# SB.net
KiCad netlist of a schematic drawn in EAGLE
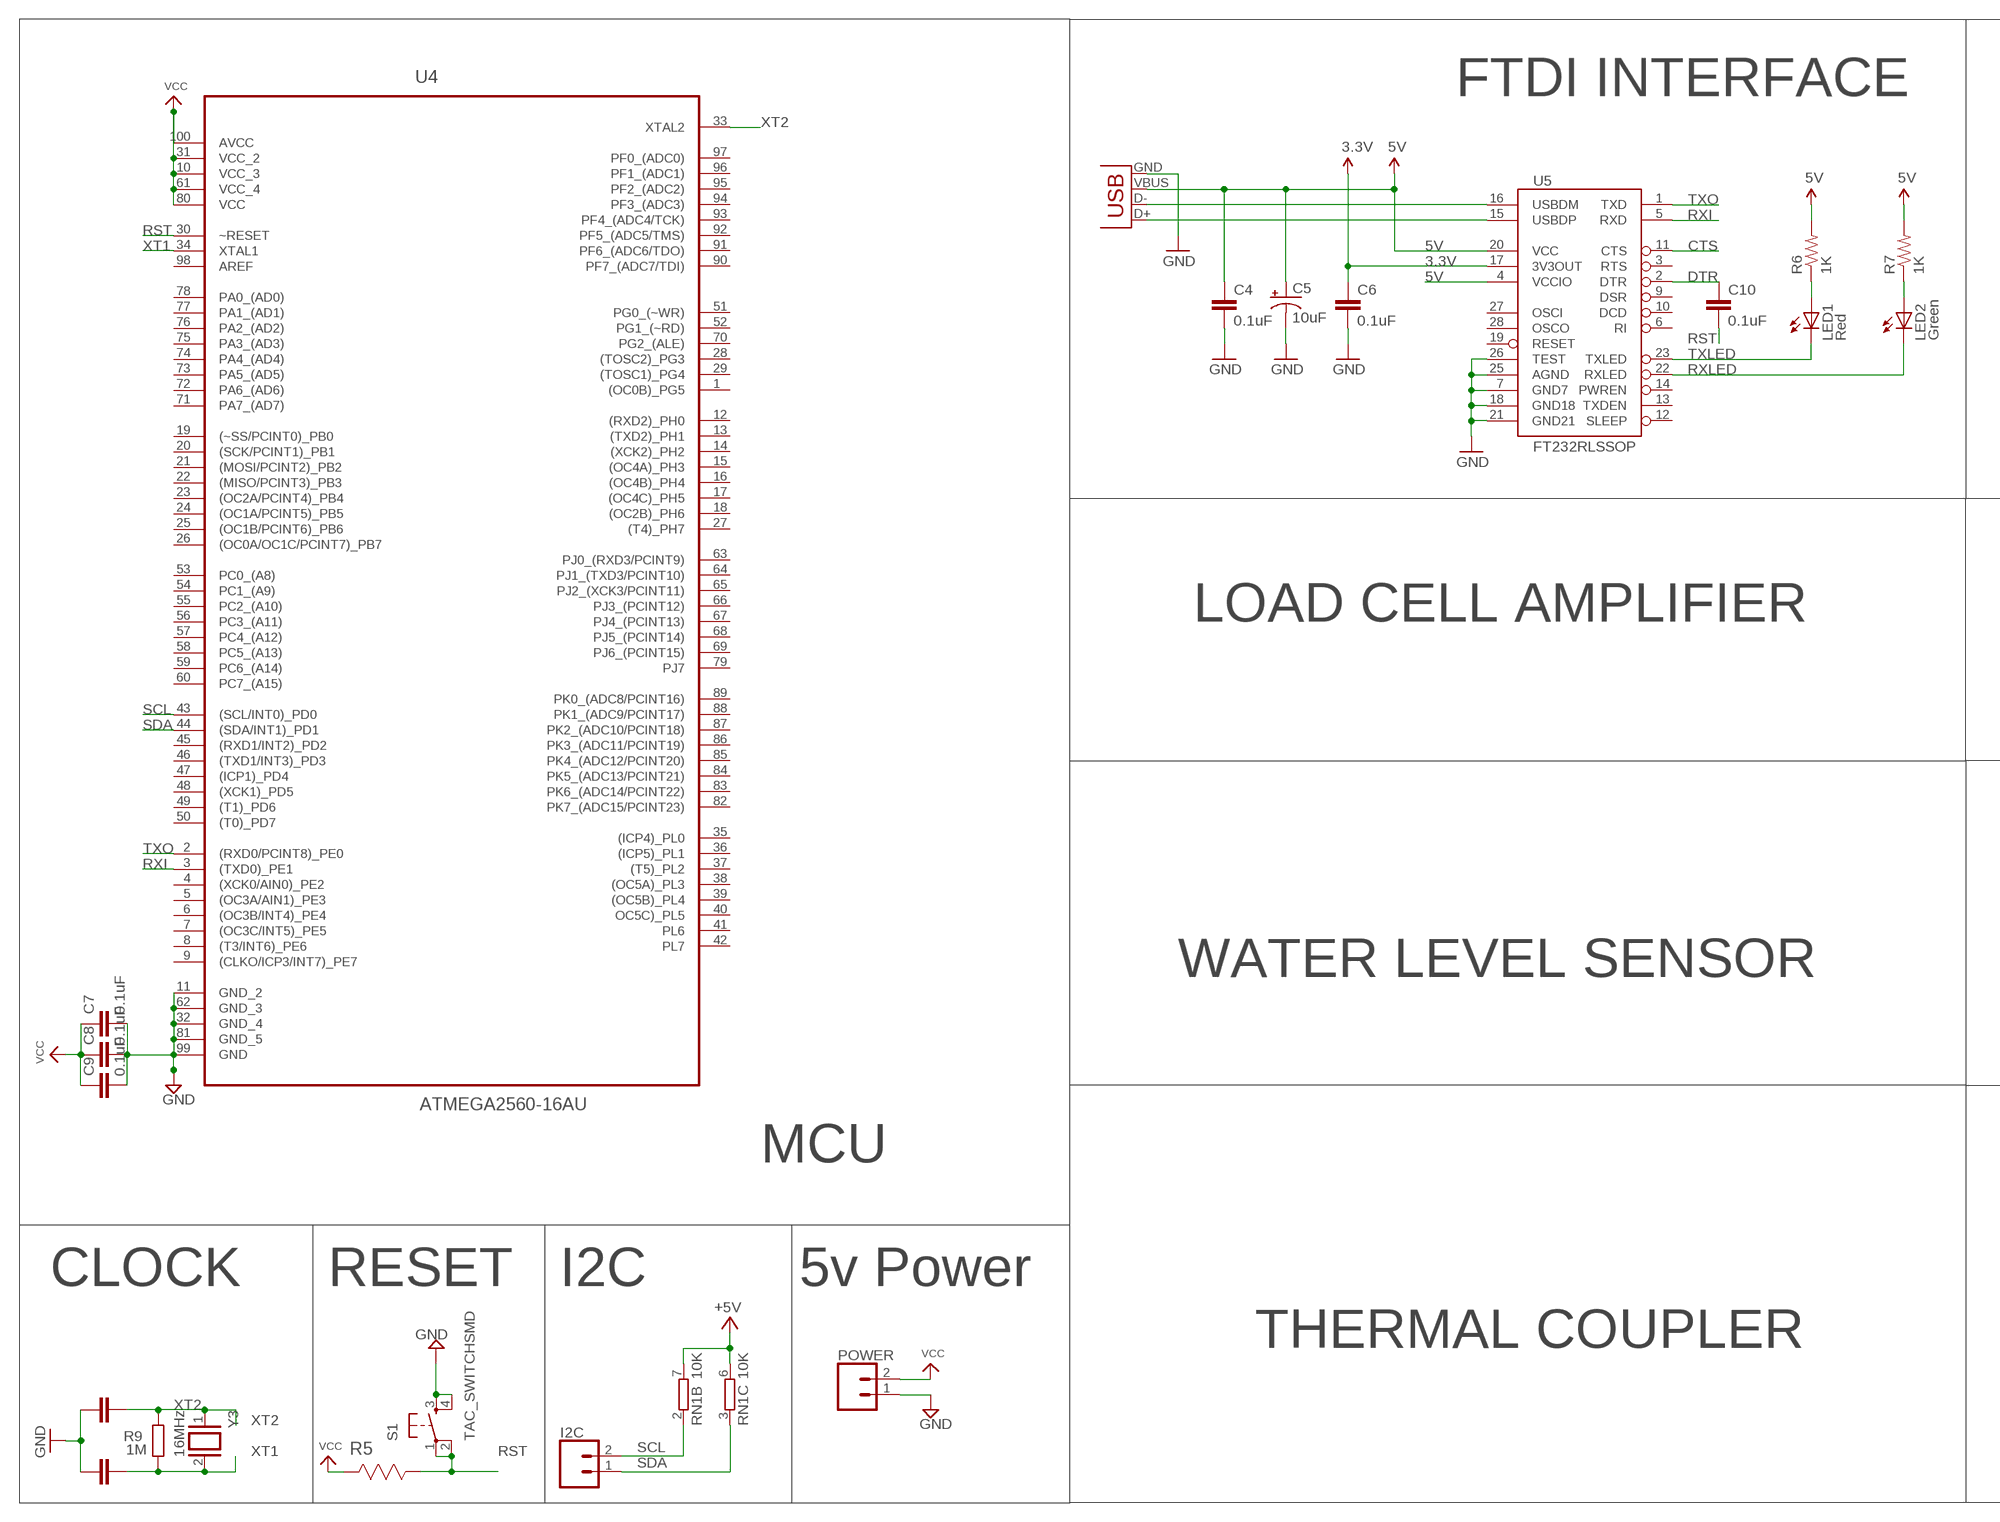
[diagram p0: schematic, sheet 1, part 1 of 2]
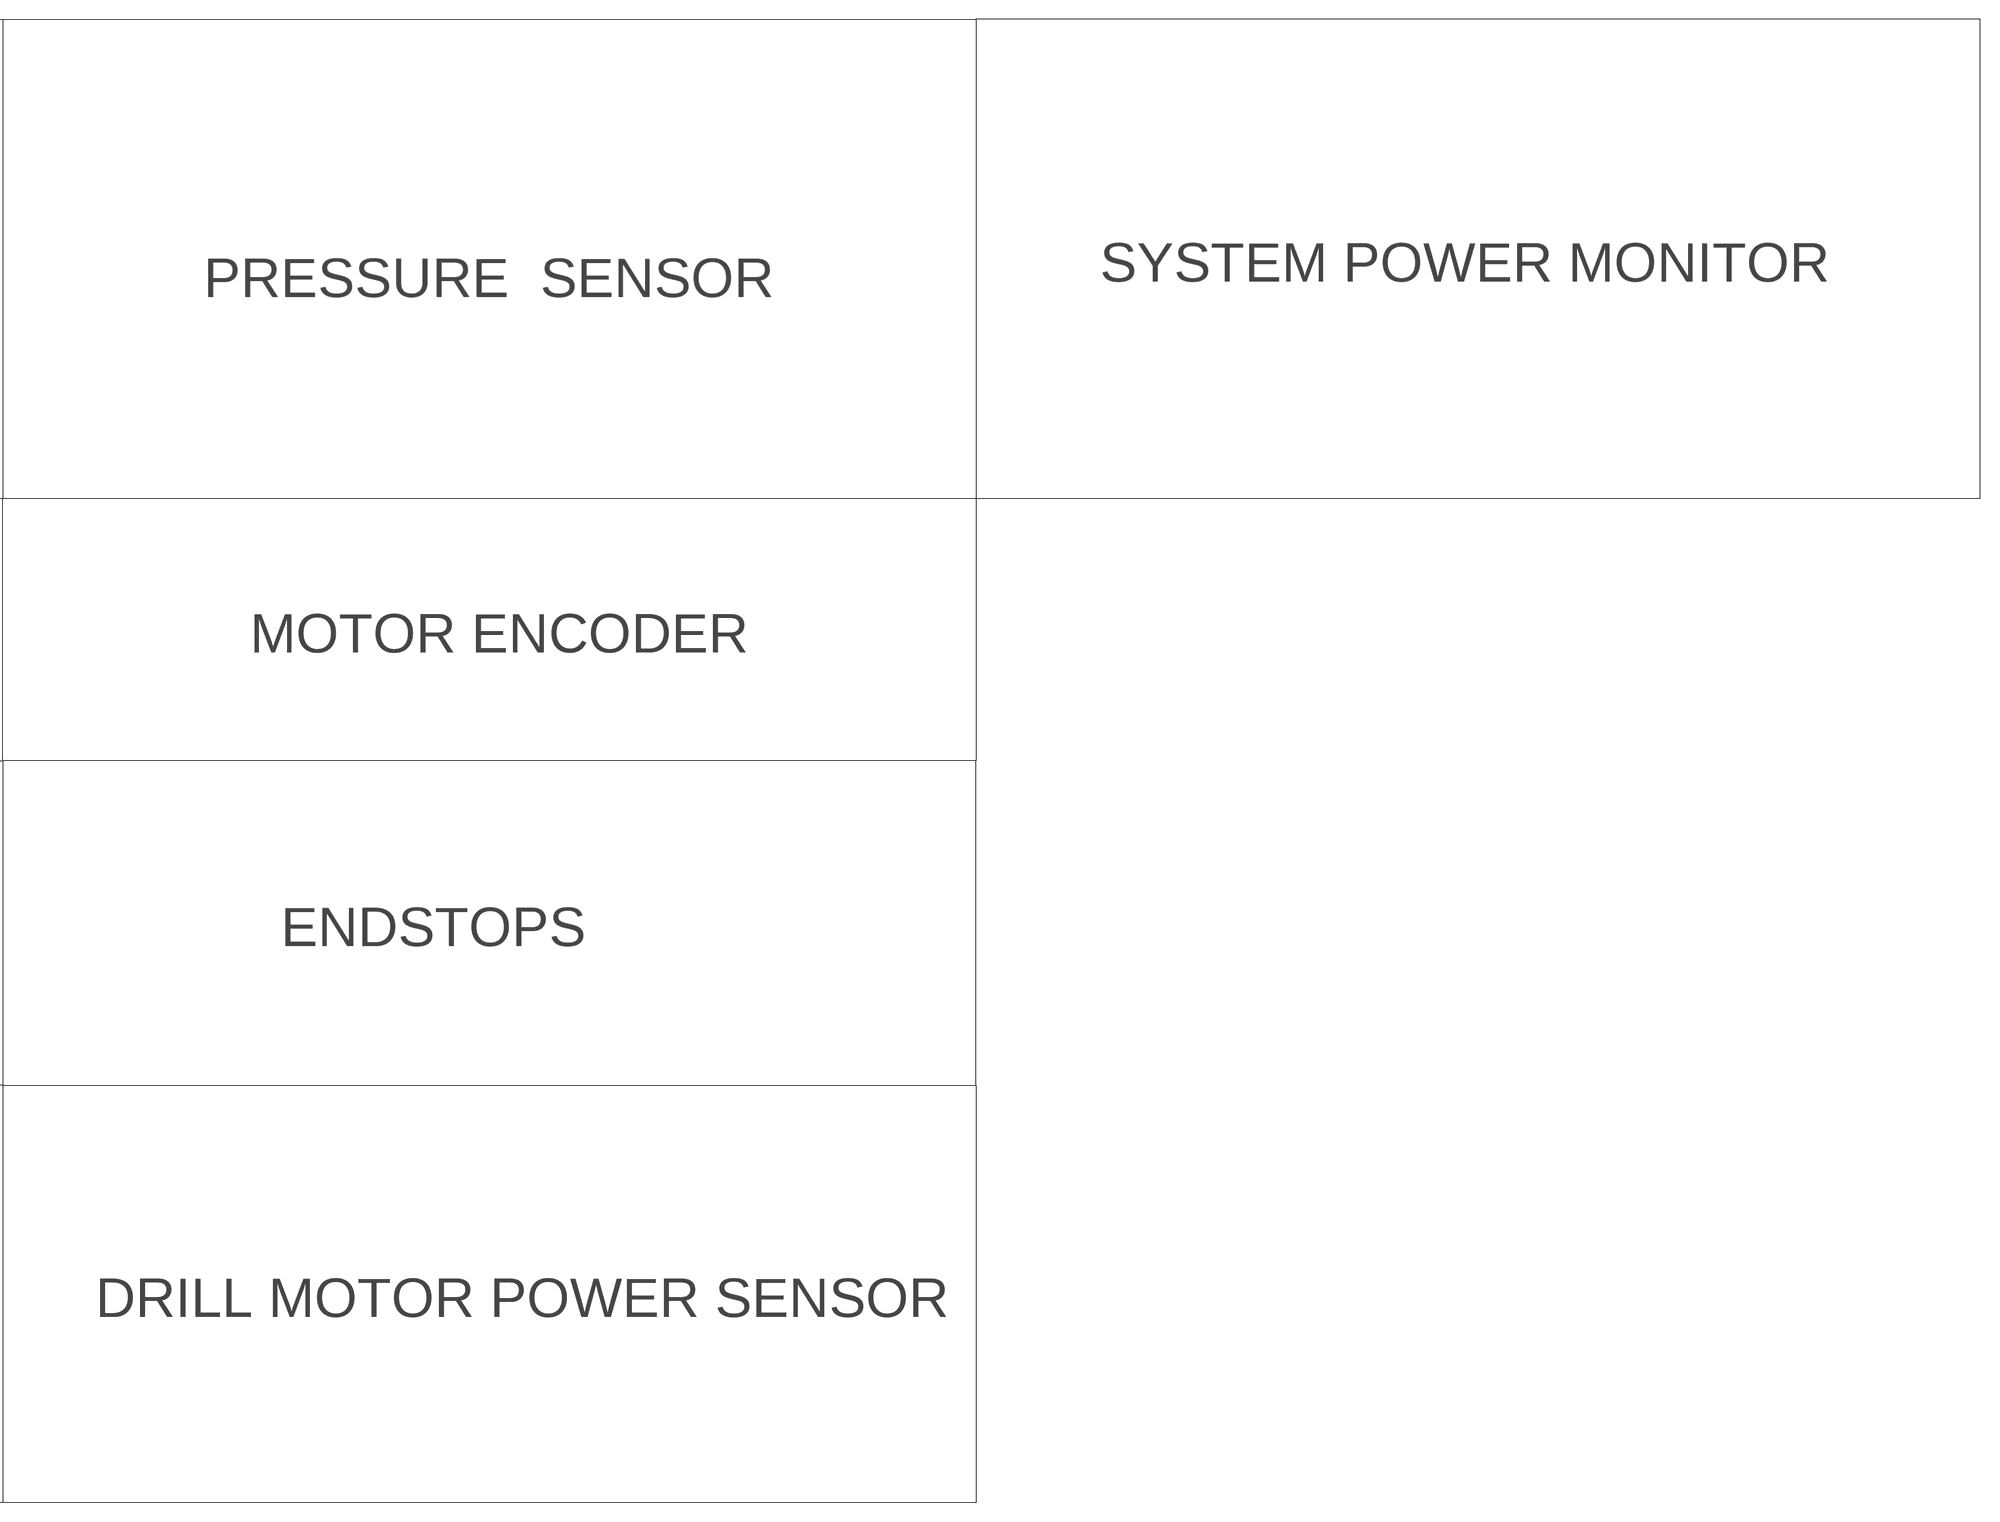
[diagram p1: schematic, sheet 1, part 2 of 2]

(export (version "E")
  (design (tool "Eeschema 10.0.6"))
  (components
    (comp (ref "C4")
      (value "0.1uF")
      (footprint "eagle-import:0402-CAP")
      (libsource (lib "eagle-import") (part "CAP0402-CAP"))
    )
    (comp (ref "C5")
      (value "10uF")
      (footprint "eagle-import:EIA3216")
      (libsource (lib "eagle-import") (part "CAP_POL1206"))
    )
    (comp (ref "C6")
      (value "0.1uF")
      (footprint "eagle-import:0402-CAP")
      (libsource (lib "eagle-import") (part "CAP0402-CAP"))
    )
    (comp (ref "C7")
      (value "0.1uF")
      (footprint "eagle-import:0603")
      (libsource (lib "eagle-import") (part "0.1UF-0603-25V-(+80/-20%)"))
    )
    (comp (ref "C8")
      (value "0.1uF")
      (footprint "eagle-import:0603")
      (libsource (lib "eagle-import") (part "0.1UF-0603-25V-(+80/-20%)"))
    )
    (comp (ref "C9")
      (value "0.1uF")
      (footprint "eagle-import:0603")
      (libsource (lib "eagle-import") (part "0.1UF-0603-25V-(+80/-20%)"))
    )
    (comp (ref "C10")
      (value "0.1uF")
      (footprint "eagle-import:0603")
      (libsource (lib "eagle-import") (part "0.1UF-0603-25V-(+80/-20%)"))
    )
    (comp (ref "C23")
      (value "22p")
      (footprint "eagle-import:C0603-ROUND")
      (libsource (lib "eagle-import") (part "C-EU0603-RND"))
    )
    (comp (ref "C24")
      (value "22p")
      (footprint "eagle-import:C0603-ROUND")
      (libsource (lib "eagle-import") (part "C-EU0603-RND"))
    )
    (comp (ref "I2C")
      (value "CONN_023.5MM_LOCK")
      (footprint "eagle-import:SCREWTERMINAL-3.5MM-2_LOCK")
      (libsource (lib "eagle-import") (part "CONN_023.5MM_LOCK"))
    )
    (comp (ref "LED1")
      (value "Red")
      (footprint "eagle-import:LED-0603")
      (libsource (lib "eagle-import") (part "LED0603"))
    )
    (comp (ref "LED2")
      (value "Green")
      (footprint "eagle-import:LED-0603")
      (libsource (lib "eagle-import") (part "LED0603"))
    )
    (comp (ref "POWER")
      (value "CONN_023.5MM_LOCK")
      (footprint "eagle-import:SCREWTERMINAL-3.5MM-2_LOCK")
      (libsource (lib "eagle-import") (part "CONN_023.5MM_LOCK"))
    )
    (comp (ref "R5")
      (value "CRM0805-FW-R050ELF")
      (footprint "eagle-import:RESC2013X65N")
      (fields (field (name "TOLERANCE") "±1 %"))
      (libsource (lib "eagle-import") (part "CRM0805-FW-R050ELF"))
    )
    (comp (ref "R6")
      (value "1K")
      (footprint "eagle-import:0402-RES")
      (libsource (lib "eagle-import") (part "RESISTOR0402-RES"))
    )
    (comp (ref "R7")
      (value "1K")
      (footprint "eagle-import:0402-RES")
      (libsource (lib "eagle-import") (part "RESISTOR0402-RES"))
    )
    (comp (ref "R9")
      (value "1M")
      (footprint "eagle-import:R0603-ROUND")
      (libsource (lib "eagle-import") (part "R-EU_R0603"))
    )
    (comp (ref "RN1")
      (value "10K")
      (footprint "eagle-import:CAT16")
      (libsource (lib "eagle-import") (part "4R-NCAT16"))
    )
    (comp (ref "S1")
      (value "TAC_SWITCHSMD")
      (footprint "eagle-import:TACTILE-SWITCH-SMD")
      (libsource (lib "eagle-import") (part "TAC_SWITCHSMD"))
    )
    (comp (ref "U4")
      (value "ATMEGA2560-16AU")
      (footprint "eagle-import:QFP50P1600X1600X120-100N")
      (libsource (lib "eagle-import") (part "ATMEGA2560-16AU"))
    )
    (comp (ref "U5")
      (value "FT232RLSSOP")
      (footprint "eagle-import:SSOP28DB")
      (libsource (lib "eagle-import") (part "FT232RLSSOP"))
    )
    (comp (ref "X2")
      (value "USB-SMD-NS")
      (footprint "eagle-import:USB-MINIB-NOSTOP")
      (libsource (lib "eagle-import") (part "USB-SMD-NS"))
    )
    (comp (ref "Y3")
      (value "16MHz")
      (footprint "eagle-import:QS")
      (libsource (lib "eagle-import") (part "XTAL/S"))
    )
  )
  (nets
    (net (code "1") (name "+5V") (class "Default")
      (node (ref "C7") (pin "1") (pinfunction "1_1") (pintype "passive"))
      (node (ref "C8") (pin "1") (pinfunction "1_1") (pintype "passive"))
      (node (ref "C9") (pin "1") (pinfunction "1_1") (pintype "passive"))
      (node (ref "POWER") (pin "2") (pinfunction "2_2") (pintype "passive"))
      (node (ref "R5") (pin "2") (pinfunction "R2_2") (pintype "passive"))
      (node (ref "RN1") (pin "6") (pinfunction "2_6") (pintype "passive"))
      (node (ref "RN1") (pin "7") (pinfunction "2_7") (pintype "passive"))
      (node (ref "U4") (pin "10") (pinfunction "VCC_3_10") (pintype "power_in"))
      (node (ref "U4") (pin "100") (pinfunction "AVCC_100") (pintype "power_in"))
      (node (ref "U4") (pin "31") (pinfunction "VCC_2_31") (pintype "power_in"))
      (node (ref "U4") (pin "61") (pinfunction "VCC_4_61") (pintype "power_in"))
      (node (ref "U4") (pin "80") (pinfunction "VCC_80") (pintype "power_in"))
    )
    (net (code "2") (name "/CTS") (class "Default")
      (node (ref "U5") (pin "11") (pinfunction "CTS_11") (pintype "input"))
    )
    (net (code "3") (name "/DTR") (class "Default")
      (node (ref "C10") (pin "1") (pinfunction "1_1") (pintype "passive"))
      (node (ref "U5") (pin "2") (pinfunction "DTR_2") (pintype "output"))
    )
    (net (code "4") (name "/RST") (class "Default")
      (node (ref "C10") (pin "2") (pinfunction "2_2") (pintype "passive"))
      (node (ref "R5") (pin "1") (pinfunction "R1_1") (pintype "passive"))
      (node (ref "S1") (pin "1") (pinfunction "1_1") (pintype "passive"))
      (node (ref "S1") (pin "2") (pinfunction "2_2") (pintype "passive"))
      (node (ref "U4") (pin "30") (pinfunction "~{RESET}_30") (pintype "input"))
    )
    (net (code "5") (name "/RXI") (class "Default")
      (node (ref "U4") (pin "3") (pinfunction "(TXD0)_PE1_3") (pintype "bidirectional"))
      (node (ref "U5") (pin "5") (pinfunction "RXD_5") (pintype "input"))
    )
    (net (code "6") (name "/RXLED") (class "Default")
      (node (ref "LED2") (pin "C") (pinfunction "C_C") (pintype "passive"))
      (node (ref "U5") (pin "22") (pinfunction "RXLED_22") (pintype "input"))
    )
    (net (code "7") (name "/SCL") (class "Default")
      (node (ref "I2C") (pin "2") (pinfunction "2_2") (pintype "passive"))
      (node (ref "RN1") (pin "2") (pinfunction "1_2") (pintype "passive"))
      (node (ref "U4") (pin "43") (pinfunction "(SCL/INT0)_PD0_43") (pintype "bidirectional"))
    )
    (net (code "8") (name "/SDA") (class "Default")
      (node (ref "I2C") (pin "1") (pinfunction "1_1") (pintype "passive"))
      (node (ref "RN1") (pin "3") (pinfunction "1_3") (pintype "passive"))
      (node (ref "U4") (pin "44") (pinfunction "(SDA/INT1)_PD1_44") (pintype "bidirectional"))
    )
    (net (code "9") (name "/TXLED") (class "Default")
      (node (ref "LED1") (pin "C") (pinfunction "C_C") (pintype "passive"))
      (node (ref "U5") (pin "23") (pinfunction "TXLED_23") (pintype "input"))
    )
    (net (code "10") (name "/TXO") (class "Default")
      (node (ref "U4") (pin "2") (pinfunction "(RXD0/PCINT8)_PE0_2") (pintype "bidirectional"))
      (node (ref "U5") (pin "1") (pinfunction "TXD_1") (pintype "output"))
    )
    (net (code "11") (name "/XT1") (class "Default")
      (node (ref "C23") (pin "1") (pinfunction "1_1") (pintype "passive"))
      (node (ref "R9") (pin "1") (pinfunction "1_1") (pintype "passive"))
      (node (ref "U4") (pin "34") (pinfunction "XTAL1_34") (pintype "input"))
      (node (ref "Y3") (pin "2") (pinfunction "2_2") (pintype "passive"))
    )
    (net (code "12") (name "/XT2") (class "Default")
      (node (ref "C24") (pin "1") (pinfunction "1_1") (pintype "passive"))
      (node (ref "R9") (pin "2") (pinfunction "2_2") (pintype "passive"))
      (node (ref "U4") (pin "33") (pinfunction "XTAL2_33") (pintype "output"))
      (node (ref "Y3") (pin "1") (pinfunction "1_1") (pintype "passive"))
    )
    (net (code "13") (name "3.3V") (class "Default")
      (node (ref "C6") (pin "1") (pinfunction "1_1") (pintype "passive"))
      (node (ref "U5") (pin "17") (pinfunction "3V3OUT_17") (pintype "output"))
    )
    (net (code "14") (name "5V") (class "Default")
      (node (ref "C4") (pin "1") (pinfunction "1_1") (pintype "passive"))
      (node (ref "C5") (pin "A") (pinfunction "+_A") (pintype "passive"))
      (node (ref "R6") (pin "2") (pinfunction "2_2") (pintype "passive"))
      (node (ref "R7") (pin "2") (pinfunction "2_2") (pintype "passive"))
      (node (ref "U5") (pin "20") (pinfunction "VCC_20") (pintype "power_in"))
      (node (ref "U5") (pin "4") (pinfunction "VCCIO_4") (pintype "power_in"))
      (node (ref "X2") (pin "VBUS") (pinfunction "VBUS_VBUS") (pintype "bidirectional"))
    )
    (net (code "15") (name "GND") (class "Default")
      (node (ref "C23") (pin "2") (pinfunction "2_2") (pintype "passive"))
      (node (ref "C24") (pin "2") (pinfunction "2_2") (pintype "passive"))
      (node (ref "C4") (pin "2") (pinfunction "2_2") (pintype "passive"))
      (node (ref "C5") (pin "C") (pinfunction "-_C") (pintype "passive"))
      (node (ref "C6") (pin "2") (pinfunction "2_2") (pintype "passive"))
      (node (ref "C7") (pin "2") (pinfunction "2_2") (pintype "passive"))
      (node (ref "C8") (pin "2") (pinfunction "2_2") (pintype "passive"))
      (node (ref "C9") (pin "2") (pinfunction "2_2") (pintype "passive"))
      (node (ref "POWER") (pin "1") (pinfunction "1_1") (pintype "passive"))
      (node (ref "S1") (pin "3") (pinfunction "3_3") (pintype "passive"))
      (node (ref "S1") (pin "4") (pinfunction "4_4") (pintype "passive"))
      (node (ref "U4") (pin "11") (pinfunction "GND_2_11") (pintype "passive"))
      (node (ref "U4") (pin "32") (pinfunction "GND_4_32") (pintype "passive"))
      (node (ref "U4") (pin "62") (pinfunction "GND_3_62") (pintype "passive"))
      (node (ref "U4") (pin "81") (pinfunction "GND_5_81") (pintype "passive"))
      (node (ref "U4") (pin "99") (pinfunction "GND_99") (pintype "passive"))
      (node (ref "U5") (pin "18") (pinfunction "GND18_18") (pintype "power_in"))
      (node (ref "U5") (pin "21") (pinfunction "GND21_21") (pintype "power_in"))
      (node (ref "U5") (pin "25") (pinfunction "AGND_25") (pintype "power_in"))
      (node (ref "U5") (pin "26") (pinfunction "TEST_26") (pintype "input"))
      (node (ref "U5") (pin "7") (pinfunction "GND7_7") (pintype "power_in"))
      (node (ref "X2") (pin "GND") (pinfunction "GND_GND") (pintype "bidirectional"))
    )
    (net (code "16") (name "Net-(LED1-PadA)") (class "Default")
      (node (ref "LED1") (pin "A") (pinfunction "A_A") (pintype "passive"))
      (node (ref "R6") (pin "1") (pinfunction "1_1") (pintype "passive"))
    )
    (net (code "17") (name "Net-(LED2-PadA)") (class "Default")
      (node (ref "LED2") (pin "A") (pinfunction "A_A") (pintype "passive"))
      (node (ref "R7") (pin "1") (pinfunction "1_1") (pintype "passive"))
    )
    (net (code "18") (name "Net-(U5-USBDM)") (class "Default")
      (node (ref "U5") (pin "16") (pinfunction "USBDM_16") (pintype "bidirectional"))
      (node (ref "X2") (pin "D-") (pinfunction "D-_D-") (pintype "bidirectional"))
    )
    (net (code "19") (name "Net-(U5-USBDP)") (class "Default")
      (node (ref "U5") (pin "15") (pinfunction "USBDP_15") (pintype "bidirectional"))
      (node (ref "X2") (pin "D+") (pinfunction "D+_D+") (pintype "bidirectional"))
    )
    (net (code "20") (name "unconnected-(U4-(CLKO{slash}ICP3{slash}INT7)_PE7-Pad9)") (class "Default")
      (node (ref "U4") (pin "9") (pinfunction "(CLKO/ICP3/INT7)_PE7_9") (pintype "bidirectional"))
    )
    (net (code "21") (name "unconnected-(U4-(ICP1)_PD4-Pad47)") (class "Default")
      (node (ref "U4") (pin "47") (pinfunction "(ICP1)_PD4_47") (pintype "bidirectional"))
    )
    (net (code "22") (name "unconnected-(U4-(ICP4)_PL0-Pad35)") (class "Default")
      (node (ref "U4") (pin "35") (pinfunction "(ICP4)_PL0_35") (pintype "bidirectional"))
    )
    (net (code "23") (name "unconnected-(U4-(ICP5)_PL1-Pad36)") (class "Default")
      (node (ref "U4") (pin "36") (pinfunction "(ICP5)_PL1_36") (pintype "bidirectional"))
    )
    (net (code "24") (name "unconnected-(U4-(MISO{slash}PCINT3)_PB3-Pad22)") (class "Default")
      (node (ref "U4") (pin "22") (pinfunction "(MISO/PCINT3)_PB3_22") (pintype "bidirectional"))
    )
    (net (code "25") (name "unconnected-(U4-(MOSI{slash}PCINT2)_PB2-Pad21)") (class "Default")
      (node (ref "U4") (pin "21") (pinfunction "(MOSI/PCINT2)_PB2_21") (pintype "bidirectional"))
    )
    (net (code "26") (name "unconnected-(U4-(OC0A{slash}OC1C{slash}PCINT7)_PB7-Pad26)") (class "Default")
      (node (ref "U4") (pin "26") (pinfunction "(OC0A/OC1C/PCINT7)_PB7_26") (pintype "bidirectional"))
    )
    (net (code "27") (name "unconnected-(U4-(OC0B)_PG5-Pad1)") (class "Default")
      (node (ref "U4") (pin "1") (pinfunction "(OC0B)_PG5_1") (pintype "bidirectional"))
    )
    (net (code "28") (name "unconnected-(U4-(OC1A{slash}PCINT5)_PB5-Pad24)") (class "Default")
      (node (ref "U4") (pin "24") (pinfunction "(OC1A/PCINT5)_PB5_24") (pintype "bidirectional"))
    )
    (net (code "29") (name "unconnected-(U4-(OC1B{slash}PCINT6)_PB6-Pad25)") (class "Default")
      (node (ref "U4") (pin "25") (pinfunction "(OC1B/PCINT6)_PB6_25") (pintype "bidirectional"))
    )
    (net (code "30") (name "unconnected-(U4-(OC2A{slash}PCINT4)_PB4-Pad23)") (class "Default")
      (node (ref "U4") (pin "23") (pinfunction "(OC2A/PCINT4)_PB4_23") (pintype "bidirectional"))
    )
    (net (code "31") (name "unconnected-(U4-(OC2B)_PH6-Pad18)") (class "Default")
      (node (ref "U4") (pin "18") (pinfunction "(OC2B)_PH6_18") (pintype "bidirectional"))
    )
    (net (code "32") (name "unconnected-(U4-(OC3A{slash}AIN1)_PE3-Pad5)") (class "Default")
      (node (ref "U4") (pin "5") (pinfunction "(OC3A/AIN1)_PE3_5") (pintype "bidirectional"))
    )
    (net (code "33") (name "unconnected-(U4-(OC3B{slash}INT4)_PE4-Pad6)") (class "Default")
      (node (ref "U4") (pin "6") (pinfunction "(OC3B/INT4)_PE4_6") (pintype "bidirectional"))
    )
    (net (code "34") (name "unconnected-(U4-(OC3C{slash}INT5)_PE5-Pad7)") (class "Default")
      (node (ref "U4") (pin "7") (pinfunction "(OC3C/INT5)_PE5_7") (pintype "bidirectional"))
    )
    (net (code "35") (name "unconnected-(U4-(OC4A)_PH3-Pad15)") (class "Default")
      (node (ref "U4") (pin "15") (pinfunction "(OC4A)_PH3_15") (pintype "bidirectional"))
    )
    (net (code "36") (name "unconnected-(U4-(OC4B)_PH4-Pad16)") (class "Default")
      (node (ref "U4") (pin "16") (pinfunction "(OC4B)_PH4_16") (pintype "bidirectional"))
    )
    (net (code "37") (name "unconnected-(U4-(OC4C)_PH5-Pad17)") (class "Default")
      (node (ref "U4") (pin "17") (pinfunction "(OC4C)_PH5_17") (pintype "bidirectional"))
    )
    (net (code "38") (name "unconnected-(U4-(OC5A)_PL3-Pad38)") (class "Default")
      (node (ref "U4") (pin "38") (pinfunction "(OC5A)_PL3_38") (pintype "bidirectional"))
    )
    (net (code "39") (name "unconnected-(U4-(OC5B)_PL4-Pad39)") (class "Default")
      (node (ref "U4") (pin "39") (pinfunction "(OC5B)_PL4_39") (pintype "bidirectional"))
    )
    (net (code "40") (name "unconnected-(U4-(RXD1{slash}INT2)_PD2-Pad45)") (class "Default")
      (node (ref "U4") (pin "45") (pinfunction "(RXD1/INT2)_PD2_45") (pintype "bidirectional"))
    )
    (net (code "41") (name "unconnected-(U4-(RXD2)_PH0-Pad12)") (class "Default")
      (node (ref "U4") (pin "12") (pinfunction "(RXD2)_PH0_12") (pintype "bidirectional"))
    )
    (net (code "42") (name "unconnected-(U4-(SCK{slash}PCINT1)_PB1-Pad20)") (class "Default")
      (node (ref "U4") (pin "20") (pinfunction "(SCK/PCINT1)_PB1_20") (pintype "bidirectional"))
    )
    (net (code "43") (name "unconnected-(U4-(T0)_PD7-Pad50)") (class "Default")
      (node (ref "U4") (pin "50") (pinfunction "(T0)_PD7_50") (pintype "bidirectional"))
    )
    (net (code "44") (name "unconnected-(U4-(T1)_PD6-Pad49)") (class "Default")
      (node (ref "U4") (pin "49") (pinfunction "(T1)_PD6_49") (pintype "bidirectional"))
    )
    (net (code "45") (name "unconnected-(U4-(T3{slash}INT6)_PE6-Pad8)") (class "Default")
      (node (ref "U4") (pin "8") (pinfunction "(T3/INT6)_PE6_8") (pintype "bidirectional"))
    )
    (net (code "46") (name "unconnected-(U4-(T4)_PH7-Pad27)") (class "Default")
      (node (ref "U4") (pin "27") (pinfunction "(T4)_PH7_27") (pintype "bidirectional"))
    )
    (net (code "47") (name "unconnected-(U4-(T5)_PL2-Pad37)") (class "Default")
      (node (ref "U4") (pin "37") (pinfunction "(T5)_PL2_37") (pintype "bidirectional"))
    )
    (net (code "48") (name "unconnected-(U4-(TOSC1)_PG4-Pad29)") (class "Default")
      (node (ref "U4") (pin "29") (pinfunction "(TOSC1)_PG4_29") (pintype "bidirectional"))
    )
    (net (code "49") (name "unconnected-(U4-(TOSC2)_PG3-Pad28)") (class "Default")
      (node (ref "U4") (pin "28") (pinfunction "(TOSC2)_PG3_28") (pintype "bidirectional"))
    )
    (net (code "50") (name "unconnected-(U4-(TXD1{slash}INT3)_PD3-Pad46)") (class "Default")
      (node (ref "U4") (pin "46") (pinfunction "(TXD1/INT3)_PD3_46") (pintype "bidirectional"))
    )
    (net (code "51") (name "unconnected-(U4-(TXD2)_PH1-Pad13)") (class "Default")
      (node (ref "U4") (pin "13") (pinfunction "(TXD2)_PH1_13") (pintype "bidirectional"))
    )
    (net (code "52") (name "unconnected-(U4-(XCK0{slash}AIN0)_PE2-Pad4)") (class "Default")
      (node (ref "U4") (pin "4") (pinfunction "(XCK0/AIN0)_PE2_4") (pintype "bidirectional"))
    )
    (net (code "53") (name "unconnected-(U4-(XCK1)_PD5-Pad48)") (class "Default")
      (node (ref "U4") (pin "48") (pinfunction "(XCK1)_PD5_48") (pintype "bidirectional"))
    )
    (net (code "54") (name "unconnected-(U4-(XCK2)_PH2-Pad14)") (class "Default")
      (node (ref "U4") (pin "14") (pinfunction "(XCK2)_PH2_14") (pintype "bidirectional"))
    )
    (net (code "55") (name "unconnected-(U4-(~{SS{slash}PCINT0})_PB0-Pad19)") (class "Default")
      (node (ref "U4") (pin "19") (pinfunction "(~{SS/PCINT0})_PB0_19") (pintype "bidirectional"))
    )
    (net (code "56") (name "unconnected-(U4-AREF-Pad98)") (class "Default")
      (node (ref "U4") (pin "98") (pinfunction "AREF_98") (pintype "input"))
    )
    (net (code "57") (name "unconnected-(U4-OC5C)_PL5-Pad40)") (class "Default")
      (node (ref "U4") (pin "40") (pinfunction "OC5C)_PL5_40") (pintype "bidirectional"))
    )
    (net (code "58") (name "unconnected-(U4-PA0_(AD0)-Pad78)") (class "Default")
      (node (ref "U4") (pin "78") (pinfunction "PA0_(AD0)_78") (pintype "bidirectional"))
    )
    (net (code "59") (name "unconnected-(U4-PA1_(AD1)-Pad77)") (class "Default")
      (node (ref "U4") (pin "77") (pinfunction "PA1_(AD1)_77") (pintype "bidirectional"))
    )
    (net (code "60") (name "unconnected-(U4-PA2_(AD2)-Pad76)") (class "Default")
      (node (ref "U4") (pin "76") (pinfunction "PA2_(AD2)_76") (pintype "bidirectional"))
    )
    (net (code "61") (name "unconnected-(U4-PA3_(AD3)-Pad75)") (class "Default")
      (node (ref "U4") (pin "75") (pinfunction "PA3_(AD3)_75") (pintype "bidirectional"))
    )
    (net (code "62") (name "unconnected-(U4-PA4_(AD4)-Pad74)") (class "Default")
      (node (ref "U4") (pin "74") (pinfunction "PA4_(AD4)_74") (pintype "bidirectional"))
    )
    (net (code "63") (name "unconnected-(U4-PA5_(AD5)-Pad73)") (class "Default")
      (node (ref "U4") (pin "73") (pinfunction "PA5_(AD5)_73") (pintype "bidirectional"))
    )
    (net (code "64") (name "unconnected-(U4-PA6_(AD6)-Pad72)") (class "Default")
      (node (ref "U4") (pin "72") (pinfunction "PA6_(AD6)_72") (pintype "bidirectional"))
    )
    (net (code "65") (name "unconnected-(U4-PA7_(AD7)-Pad71)") (class "Default")
      (node (ref "U4") (pin "71") (pinfunction "PA7_(AD7)_71") (pintype "bidirectional"))
    )
    (net (code "66") (name "unconnected-(U4-PC0_(A8)-Pad53)") (class "Default")
      (node (ref "U4") (pin "53") (pinfunction "PC0_(A8)_53") (pintype "bidirectional"))
    )
    (net (code "67") (name "unconnected-(U4-PC1_(A9)-Pad54)") (class "Default")
      (node (ref "U4") (pin "54") (pinfunction "PC1_(A9)_54") (pintype "bidirectional"))
    )
    (net (code "68") (name "unconnected-(U4-PC2_(A10)-Pad55)") (class "Default")
      (node (ref "U4") (pin "55") (pinfunction "PC2_(A10)_55") (pintype "bidirectional"))
    )
    (net (code "69") (name "unconnected-(U4-PC3_(A11)-Pad56)") (class "Default")
      (node (ref "U4") (pin "56") (pinfunction "PC3_(A11)_56") (pintype "bidirectional"))
    )
    (net (code "70") (name "unconnected-(U4-PC4_(A12)-Pad57)") (class "Default")
      (node (ref "U4") (pin "57") (pinfunction "PC4_(A12)_57") (pintype "bidirectional"))
    )
    (net (code "71") (name "unconnected-(U4-PC5_(A13)-Pad58)") (class "Default")
      (node (ref "U4") (pin "58") (pinfunction "PC5_(A13)_58") (pintype "bidirectional"))
    )
    (net (code "72") (name "unconnected-(U4-PC6_(A14)-Pad59)") (class "Default")
      (node (ref "U4") (pin "59") (pinfunction "PC6_(A14)_59") (pintype "bidirectional"))
    )
    (net (code "73") (name "unconnected-(U4-PC7_(A15)-Pad60)") (class "Default")
      (node (ref "U4") (pin "60") (pinfunction "PC7_(A15)_60") (pintype "bidirectional"))
    )
    (net (code "74") (name "unconnected-(U4-PF0_(ADC0)-Pad97)") (class "Default")
      (node (ref "U4") (pin "97") (pinfunction "PF0_(ADC0)_97") (pintype "bidirectional"))
    )
    (net (code "75") (name "unconnected-(U4-PF1_(ADC1)-Pad96)") (class "Default")
      (node (ref "U4") (pin "96") (pinfunction "PF1_(ADC1)_96") (pintype "bidirectional"))
    )
    (net (code "76") (name "unconnected-(U4-PF2_(ADC2)-Pad95)") (class "Default")
      (node (ref "U4") (pin "95") (pinfunction "PF2_(ADC2)_95") (pintype "bidirectional"))
    )
    (net (code "77") (name "unconnected-(U4-PF3_(ADC3)-Pad94)") (class "Default")
      (node (ref "U4") (pin "94") (pinfunction "PF3_(ADC3)_94") (pintype "bidirectional"))
    )
    (net (code "78") (name "unconnected-(U4-PF4_(ADC4{slash}TCK)-Pad93)") (class "Default")
      (node (ref "U4") (pin "93") (pinfunction "PF4_(ADC4/TCK)_93") (pintype "bidirectional"))
    )
    (net (code "79") (name "unconnected-(U4-PF5_(ADC5{slash}TMS)-Pad92)") (class "Default")
      (node (ref "U4") (pin "92") (pinfunction "PF5_(ADC5/TMS)_92") (pintype "bidirectional"))
    )
    (net (code "80") (name "unconnected-(U4-PF6_(ADC6{slash}TDO)-Pad91)") (class "Default")
      (node (ref "U4") (pin "91") (pinfunction "PF6_(ADC6/TDO)_91") (pintype "bidirectional"))
    )
    (net (code "81") (name "unconnected-(U4-PF7_(ADC7{slash}TDI)-Pad90)") (class "Default")
      (node (ref "U4") (pin "90") (pinfunction "PF7_(ADC7/TDI)_90") (pintype "bidirectional"))
    )
    (net (code "82") (name "unconnected-(U4-PG0_(~{WR})-Pad51)") (class "Default")
      (node (ref "U4") (pin "51") (pinfunction "PG0_(~{WR})_51") (pintype "bidirectional"))
    )
    (net (code "83") (name "unconnected-(U4-PG1_(~{RD})-Pad52)") (class "Default")
      (node (ref "U4") (pin "52") (pinfunction "PG1_(~{RD})_52") (pintype "bidirectional"))
    )
    (net (code "84") (name "unconnected-(U4-PG2_(ALE)-Pad70)") (class "Default")
      (node (ref "U4") (pin "70") (pinfunction "PG2_(ALE)_70") (pintype "bidirectional"))
    )
    (net (code "85") (name "unconnected-(U4-PJ0_(RXD3{slash}PCINT9)-Pad63)") (class "Default")
      (node (ref "U4") (pin "63") (pinfunction "PJ0_(RXD3/PCINT9)_63") (pintype "bidirectional"))
    )
    (net (code "86") (name "unconnected-(U4-PJ1_(TXD3{slash}PCINT10)-Pad64)") (class "Default")
      (node (ref "U4") (pin "64") (pinfunction "PJ1_(TXD3/PCINT10)_64") (pintype "bidirectional"))
    )
    (net (code "87") (name "unconnected-(U4-PJ2_(XCK3{slash}PCINT11)-Pad65)") (class "Default")
      (node (ref "U4") (pin "65") (pinfunction "PJ2_(XCK3/PCINT11)_65") (pintype "bidirectional"))
    )
    (net (code "88") (name "unconnected-(U4-PJ3_(PCINT12)-Pad66)") (class "Default")
      (node (ref "U4") (pin "66") (pinfunction "PJ3_(PCINT12)_66") (pintype "bidirectional"))
    )
    (net (code "89") (name "unconnected-(U4-PJ4_(PCINT13)-Pad67)") (class "Default")
      (node (ref "U4") (pin "67") (pinfunction "PJ4_(PCINT13)_67") (pintype "bidirectional"))
    )
    (net (code "90") (name "unconnected-(U4-PJ5_(PCINT14)-Pad68)") (class "Default")
      (node (ref "U4") (pin "68") (pinfunction "PJ5_(PCINT14)_68") (pintype "bidirectional"))
    )
    (net (code "91") (name "unconnected-(U4-PJ6_(PCINT15)-Pad69)") (class "Default")
      (node (ref "U4") (pin "69") (pinfunction "PJ6_(PCINT15)_69") (pintype "bidirectional"))
    )
    (net (code "92") (name "unconnected-(U4-PJ7-Pad79)") (class "Default")
      (node (ref "U4") (pin "79") (pinfunction "PJ7_79") (pintype "bidirectional"))
    )
    (net (code "93") (name "unconnected-(U4-PK0_(ADC8{slash}PCINT16)-Pad89)") (class "Default")
      (node (ref "U4") (pin "89") (pinfunction "PK0_(ADC8/PCINT16)_89") (pintype "bidirectional"))
    )
    (net (code "94") (name "unconnected-(U4-PK1_(ADC9{slash}PCINT17)-Pad88)") (class "Default")
      (node (ref "U4") (pin "88") (pinfunction "PK1_(ADC9/PCINT17)_88") (pintype "bidirectional"))
    )
    (net (code "95") (name "unconnected-(U4-PK2_(ADC10{slash}PCINT18)-Pad87)") (class "Default")
      (node (ref "U4") (pin "87") (pinfunction "PK2_(ADC10/PCINT18)_87") (pintype "bidirectional"))
    )
    (net (code "96") (name "unconnected-(U4-PK3_(ADC11{slash}PCINT19)-Pad86)") (class "Default")
      (node (ref "U4") (pin "86") (pinfunction "PK3_(ADC11/PCINT19)_86") (pintype "bidirectional"))
    )
    (net (code "97") (name "unconnected-(U4-PK4_(ADC12{slash}PCINT20)-Pad85)") (class "Default")
      (node (ref "U4") (pin "85") (pinfunction "PK4_(ADC12/PCINT20)_85") (pintype "bidirectional"))
    )
    (net (code "98") (name "unconnected-(U4-PK5_(ADC13{slash}PCINT21)-Pad84)") (class "Default")
      (node (ref "U4") (pin "84") (pinfunction "PK5_(ADC13/PCINT21)_84") (pintype "bidirectional"))
    )
    (net (code "99") (name "unconnected-(U4-PK6_(ADC14{slash}PCINT22)-Pad83)") (class "Default")
      (node (ref "U4") (pin "83") (pinfunction "PK6_(ADC14/PCINT22)_83") (pintype "bidirectional"))
    )
    (net (code "100") (name "unconnected-(U4-PK7_(ADC15{slash}PCINT23)-Pad82)") (class "Default")
      (node (ref "U4") (pin "82") (pinfunction "PK7_(ADC15/PCINT23)_82") (pintype "bidirectional"))
    )
    (net (code "101") (name "unconnected-(U4-PL6-Pad41)") (class "Default")
      (node (ref "U4") (pin "41") (pinfunction "PL6_41") (pintype "bidirectional"))
    )
    (net (code "102") (name "unconnected-(U4-PL7-Pad42)") (class "Default")
      (node (ref "U4") (pin "42") (pinfunction "PL7_42") (pintype "bidirectional"))
    )
    (net (code "103") (name "unconnected-(U5-DCD-Pad10)") (class "Default")
      (node (ref "U5") (pin "10") (pinfunction "DCD_10") (pintype "input"))
    )
    (net (code "104") (name "unconnected-(U5-DSR-Pad9)") (class "Default")
      (node (ref "U5") (pin "9") (pinfunction "DSR_9") (pintype "input"))
    )
    (net (code "105") (name "unconnected-(U5-OSCI-Pad27)") (class "Default")
      (node (ref "U5") (pin "27") (pinfunction "OSCI_27") (pintype "input"))
    )
    (net (code "106") (name "unconnected-(U5-OSCO-Pad28)") (class "Default")
      (node (ref "U5") (pin "28") (pinfunction "OSCO_28") (pintype "output"))
    )
    (net (code "107") (name "unconnected-(U5-PWREN-Pad14)") (class "Default")
      (node (ref "U5") (pin "14") (pinfunction "PWREN_14") (pintype "input"))
    )
    (net (code "108") (name "unconnected-(U5-RESET-Pad19)") (class "Default")
      (node (ref "U5") (pin "19") (pinfunction "RESET_19") (pintype "input"))
    )
    (net (code "109") (name "unconnected-(U5-RI-Pad6)") (class "Default")
      (node (ref "U5") (pin "6") (pinfunction "RI_6") (pintype "input"))
    )
    (net (code "110") (name "unconnected-(U5-RTS-Pad3)") (class "Default")
      (node (ref "U5") (pin "3") (pinfunction "RTS_3") (pintype "output"))
    )
    (net (code "111") (name "unconnected-(U5-SLEEP-Pad12)") (class "Default")
      (node (ref "U5") (pin "12") (pinfunction "SLEEP_12") (pintype "input"))
    )
    (net (code "112") (name "unconnected-(U5-TXDEN-Pad13)") (class "Default")
      (node (ref "U5") (pin "13") (pinfunction "TXDEN_13") (pintype "input"))
    )
  )
)
